# circuit.net
KiCad netlist of a schematic drawn in EAGLE
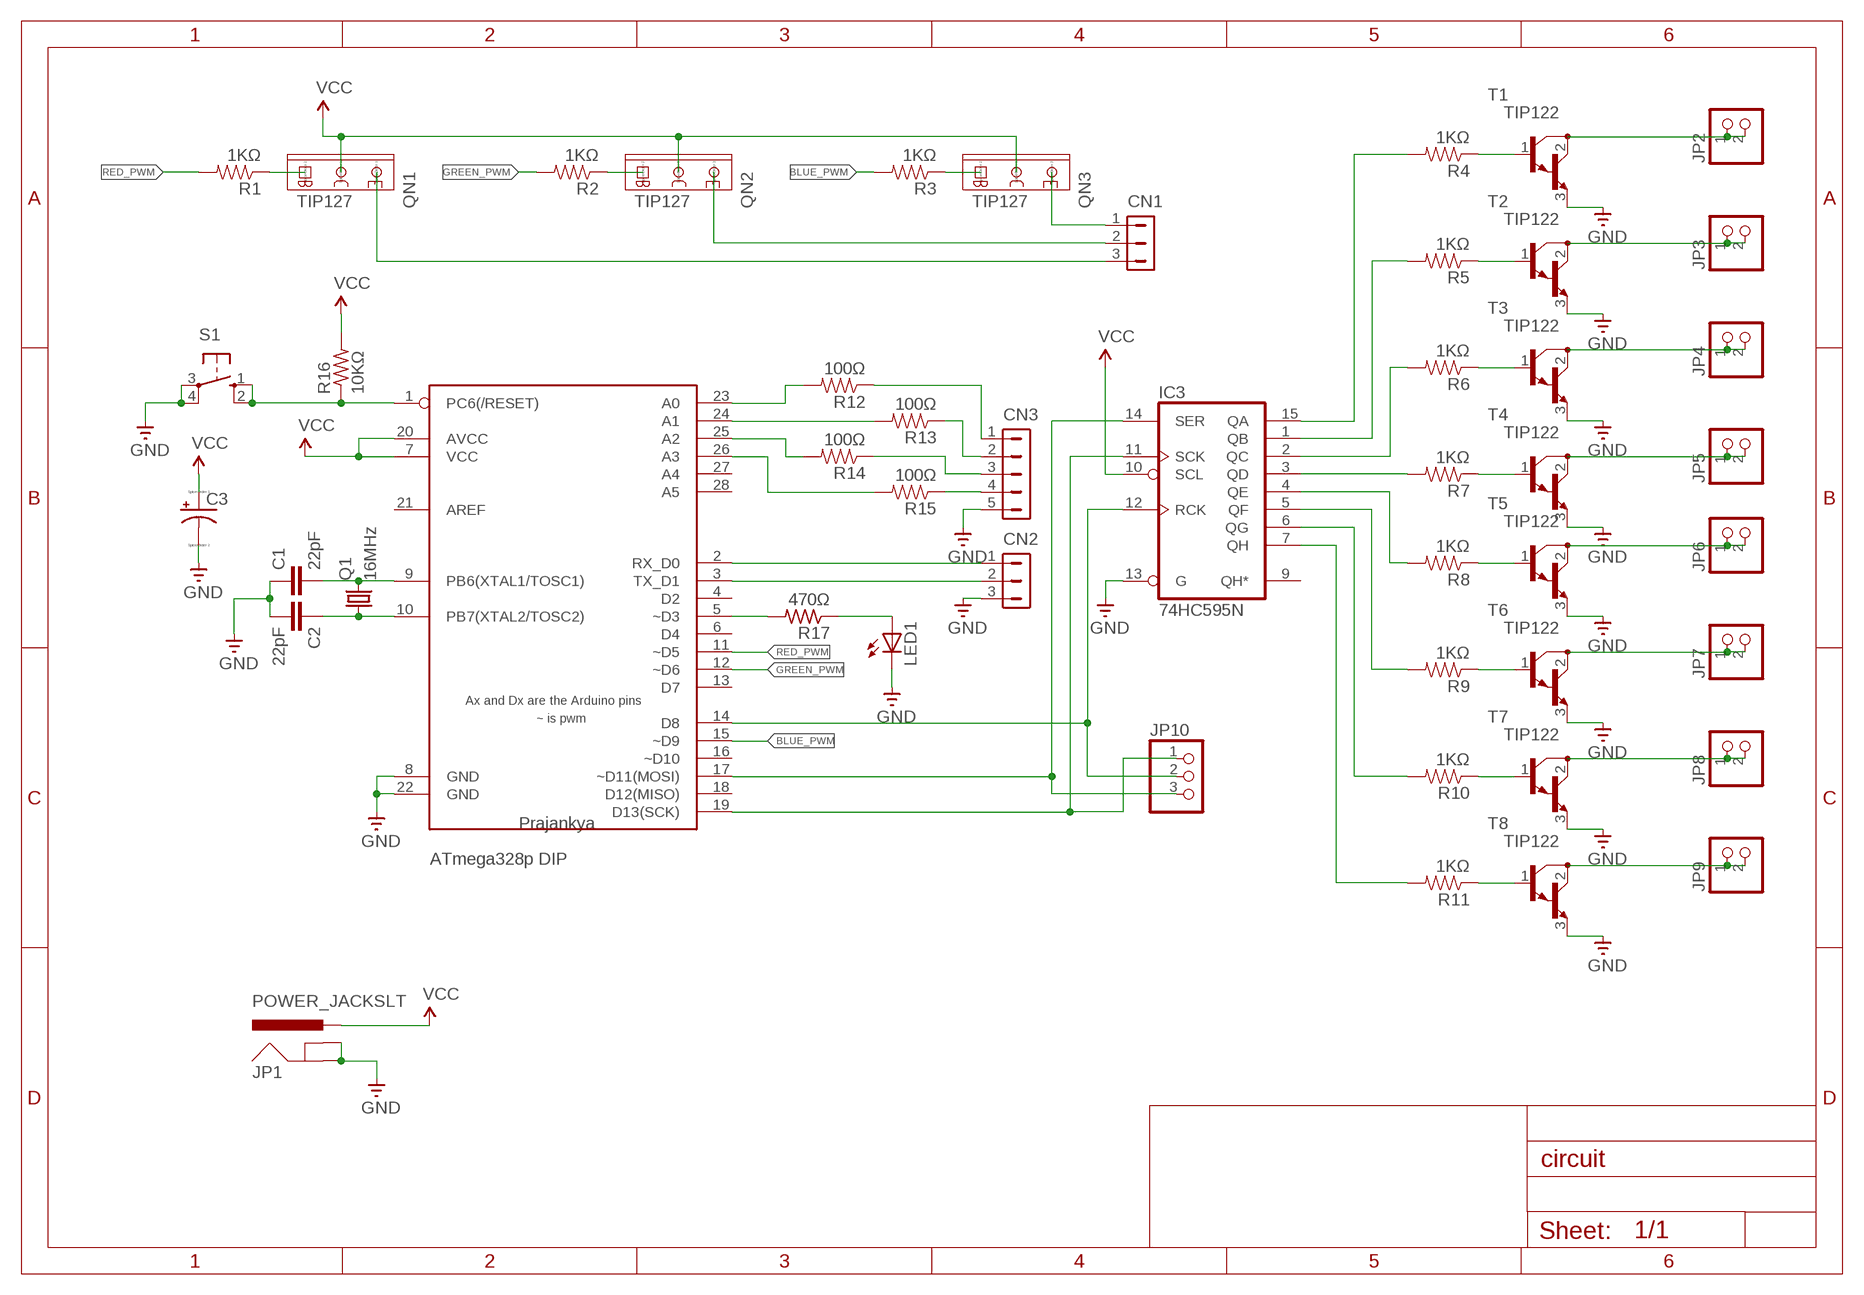
[diagram p0: schematic, sheet 1]

(export (version "E")
  (design (tool "Eeschema 10.0.6"))
  (components
    (comp (ref "C1")
      (value "22pF")
      (footprint "eagle-import:C025-025X050")
      (libsource (lib "eagle-import") (part "C-EU025-025X050"))
    )
    (comp (ref "C2")
      (value "22pF")
      (footprint "eagle-import:C025-025X050")
      (libsource (lib "eagle-import") (part "C-EU025-025X050"))
    )
    (comp (ref "C3")
      (value "CPOL-USTT2D6L")
      (footprint "eagle-import:TT2D6L")
      (libsource (lib "eagle-import") (part "CPOL-USTT2D6L"))
    )
    (comp (ref "CN1")
      (value "HDR-1X3-70543-?")
      (footprint "eagle-import:70543-03")
      (libsource (lib "eagle-import") (part "HDR-1X3-70543-?"))
    )
    (comp (ref "CN2")
      (value "HDR-1X3-70543-?")
      (footprint "eagle-import:70543-03")
      (libsource (lib "eagle-import") (part "HDR-1X3-70543-?"))
    )
    (comp (ref "CN3")
      (value "HDR-1X5-70543-?")
      (footprint "eagle-import:70543-05")
      (libsource (lib "eagle-import") (part "HDR-1X5-70543-?"))
    )
    (comp (ref "IC3")
      (value "74HC595N")
      (footprint "eagle-import:DIL16")
      (libsource (lib "eagle-import") (part "74595NHC"))
    )
    (comp (ref "JP1")
      (value "POWER_JACKSLT")
      (footprint "eagle-import:POWER_JACK_SLOT")
      (libsource (lib "eagle-import") (part "POWER_JACKSLT"))
    )
    (comp (ref "JP2")
      (value "PINHD-1X2")
      (footprint "eagle-import:1X02")
      (libsource (lib "eagle-import") (part "PINHD-1X2"))
    )
    (comp (ref "JP3")
      (value "PINHD-1X2")
      (footprint "eagle-import:1X02")
      (libsource (lib "eagle-import") (part "PINHD-1X2"))
    )
    (comp (ref "JP4")
      (value "PINHD-1X2")
      (footprint "eagle-import:1X02")
      (libsource (lib "eagle-import") (part "PINHD-1X2"))
    )
    (comp (ref "JP5")
      (value "PINHD-1X2")
      (footprint "eagle-import:1X02")
      (libsource (lib "eagle-import") (part "PINHD-1X2"))
    )
    (comp (ref "JP6")
      (value "PINHD-1X2")
      (footprint "eagle-import:1X02")
      (libsource (lib "eagle-import") (part "PINHD-1X2"))
    )
    (comp (ref "JP7")
      (value "PINHD-1X2")
      (footprint "eagle-import:1X02")
      (libsource (lib "eagle-import") (part "PINHD-1X2"))
    )
    (comp (ref "JP8")
      (value "PINHD-1X2")
      (footprint "eagle-import:1X02")
      (libsource (lib "eagle-import") (part "PINHD-1X2"))
    )
    (comp (ref "JP9")
      (value "PINHD-1X2")
      (footprint "eagle-import:1X02")
      (libsource (lib "eagle-import") (part "PINHD-1X2"))
    )
    (comp (ref "JP10")
      (value "PINHD-1X3")
      (footprint "eagle-import:1X03")
      (libsource (lib "eagle-import") (part "PINHD-1X3"))
    )
    (comp (ref "LED1")
      (value "LED5MM")
      (footprint "eagle-import:LED5MM")
      (libsource (lib "eagle-import") (part "LED5MM"))
    )
    (comp (ref "Q1")
      (value "16MHz")
      (footprint "eagle-import:HC49U-V")
      (libsource (lib "eagle-import") (part "CRYSTALHC49U-V"))
    )
    (comp (ref "QN1")
      (value "TIP127")
      (footprint "eagle-import:TO220AV")
      (libsource (lib "eagle-import") (part "TIP127"))
    )
    (comp (ref "QN2")
      (value "TIP127")
      (footprint "eagle-import:TO220AV")
      (libsource (lib "eagle-import") (part "TIP127"))
    )
    (comp (ref "QN3")
      (value "TIP127")
      (footprint "eagle-import:TO220AV")
      (libsource (lib "eagle-import") (part "TIP127"))
    )
    (comp (ref "R1")
      (value "1KΩ")
      (footprint "eagle-import:AXIAL-0.4")
      (libsource (lib "eagle-import") (part "RESISTORPTH-1/4W"))
    )
    (comp (ref "R2")
      (value "1KΩ")
      (footprint "eagle-import:AXIAL-0.4")
      (libsource (lib "eagle-import") (part "RESISTORPTH-1/4W"))
    )
    (comp (ref "R3")
      (value "1KΩ")
      (footprint "eagle-import:AXIAL-0.4")
      (libsource (lib "eagle-import") (part "RESISTORPTH-1/4W"))
    )
    (comp (ref "R4")
      (value "1KΩ")
      (footprint "eagle-import:AXIAL-0.4")
      (libsource (lib "eagle-import") (part "RESISTORPTH-1/4W"))
    )
    (comp (ref "R5")
      (value "1KΩ")
      (footprint "eagle-import:AXIAL-0.4")
      (libsource (lib "eagle-import") (part "RESISTORPTH-1/4W"))
    )
    (comp (ref "R6")
      (value "1KΩ")
      (footprint "eagle-import:AXIAL-0.4")
      (libsource (lib "eagle-import") (part "RESISTORPTH-1/4W"))
    )
    (comp (ref "R7")
      (value "1KΩ")
      (footprint "eagle-import:AXIAL-0.4")
      (libsource (lib "eagle-import") (part "RESISTORPTH-1/4W"))
    )
    (comp (ref "R8")
      (value "1KΩ")
      (footprint "eagle-import:AXIAL-0.4")
      (libsource (lib "eagle-import") (part "RESISTORPTH-1/4W"))
    )
    (comp (ref "R9")
      (value "1KΩ")
      (footprint "eagle-import:AXIAL-0.4")
      (libsource (lib "eagle-import") (part "RESISTORPTH-1/4W"))
    )
    (comp (ref "R10")
      (value "1KΩ")
      (footprint "eagle-import:AXIAL-0.4")
      (libsource (lib "eagle-import") (part "RESISTORPTH-1/4W"))
    )
    (comp (ref "R11")
      (value "1KΩ")
      (footprint "eagle-import:AXIAL-0.4")
      (libsource (lib "eagle-import") (part "RESISTORPTH-1/4W"))
    )
    (comp (ref "R12")
      (value "100Ω")
      (footprint "eagle-import:AXIAL-0.4")
      (libsource (lib "eagle-import") (part "RESISTORPTH-1/4W"))
    )
    (comp (ref "R13")
      (value "100Ω")
      (footprint "eagle-import:AXIAL-0.4")
      (libsource (lib "eagle-import") (part "RESISTORPTH-1/4W"))
    )
    (comp (ref "R14")
      (value "100Ω")
      (footprint "eagle-import:AXIAL-0.4")
      (libsource (lib "eagle-import") (part "RESISTORPTH-1/4W"))
    )
    (comp (ref "R15")
      (value "100Ω")
      (footprint "eagle-import:AXIAL-0.4")
      (libsource (lib "eagle-import") (part "RESISTORPTH-1/4W"))
    )
    (comp (ref "R16")
      (value "10KΩ")
      (footprint "eagle-import:0207_10")
      (libsource (lib "eagle-import") (part "R-US_0207/10"))
    )
    (comp (ref "R17")
      (value "470Ω")
      (footprint "eagle-import:0207_12")
      (libsource (lib "eagle-import") (part "R-US_0207/12"))
    )
    (comp (ref "S1")
      (value "10-XX")
      (footprint "eagle-import:B3F-10XX")
      (fields (field (name "MPN") "B3F-1000"))
      (libsource (lib "eagle-import") (part "10-XX"))
    )
    (comp (ref "T1")
      (value "TIP122")
      (footprint "eagle-import:TO220")
      (libsource (lib "eagle-import") (part "TIP122"))
    )
    (comp (ref "T2")
      (value "TIP122")
      (footprint "eagle-import:TO220")
      (libsource (lib "eagle-import") (part "TIP122"))
    )
    (comp (ref "T3")
      (value "TIP122")
      (footprint "eagle-import:TO220")
      (libsource (lib "eagle-import") (part "TIP122"))
    )
    (comp (ref "T4")
      (value "TIP122")
      (footprint "eagle-import:TO220")
      (libsource (lib "eagle-import") (part "TIP122"))
    )
    (comp (ref "T5")
      (value "TIP122")
      (footprint "eagle-import:TO220")
      (libsource (lib "eagle-import") (part "TIP122"))
    )
    (comp (ref "T6")
      (value "TIP122")
      (footprint "eagle-import:TO220")
      (libsource (lib "eagle-import") (part "TIP122"))
    )
    (comp (ref "T7")
      (value "TIP122")
      (footprint "eagle-import:TO220")
      (libsource (lib "eagle-import") (part "TIP122"))
    )
    (comp (ref "T8")
      (value "TIP122")
      (footprint "eagle-import:TO220")
      (libsource (lib "eagle-import") (part "TIP122"))
    )
    (comp (ref "U$1")
      (value "ATMEGA328P_DIP")
      (footprint "eagle-import:ATMEGA328_CUSTOMPAD")
      (libsource (lib "eagle-import") (part "ATMEGA328P_DIP"))
    )
  )
  (nets
    (net (code "1") (name "BLUE_PWM") (class "Default")
      (node (ref "R3") (pin "P$2") (pinfunction "2_P$2") (pintype "passive"))
      (node (ref "U$1") (pin "15") (pinfunction "~{D9}_15") (pintype "bidirectional"))
    )
    (net (code "2") (name "GND") (class "Default")
      (node (ref "C1") (pin "1") (pinfunction "1_1") (pintype "passive"))
      (node (ref "C2") (pin "2") (pinfunction "2_2") (pintype "passive"))
      (node (ref "C3") (pin "-") (pinfunction "-_-") (pintype "passive"))
      (node (ref "CN2") (pin "3") (pinfunction "3_3") (pintype "passive"))
      (node (ref "CN3") (pin "5") (pinfunction "5_5") (pintype "passive"))
      (node (ref "IC3") (pin "13") (pinfunction "G_13") (pintype "input"))
      (node (ref "JP1") (pin "GND@1") (pinfunction "GNDBREAK_GND@1") (pintype "bidirectional"))
      (node (ref "JP1") (pin "GND@2") (pinfunction "GND_GND@2") (pintype "bidirectional"))
      (node (ref "LED1") (pin "K") (pinfunction "C_K") (pintype "passive"))
      (node (ref "S1") (pin "3") (pinfunction "P_3") (pintype "passive"))
      (node (ref "S1") (pin "4") (pinfunction "P1_4") (pintype "passive"))
      (node (ref "T1") (pin "3") (pinfunction "E_3") (pintype "passive"))
      (node (ref "T2") (pin "3") (pinfunction "E_3") (pintype "passive"))
      (node (ref "T3") (pin "3") (pinfunction "E_3") (pintype "passive"))
      (node (ref "T4") (pin "3") (pinfunction "E_3") (pintype "passive"))
      (node (ref "T5") (pin "3") (pinfunction "E_3") (pintype "passive"))
      (node (ref "T6") (pin "3") (pinfunction "E_3") (pintype "passive"))
      (node (ref "T7") (pin "3") (pinfunction "E_3") (pintype "passive"))
      (node (ref "T8") (pin "3") (pinfunction "E_3") (pintype "passive"))
      (node (ref "U$1") (pin "22") (pinfunction "GND_22") (pintype "power_in"))
      (node (ref "U$1") (pin "8") (pinfunction "GND_8") (pintype "power_in"))
    )
    (net (code "3") (name "GREEN_PWM") (class "Default")
      (node (ref "R2") (pin "P$2") (pinfunction "2_P$2") (pintype "passive"))
      (node (ref "U$1") (pin "12") (pinfunction "~{D6}_12") (pintype "bidirectional"))
    )
    (net (code "4") (name "Net-(CN1-Pad1)") (class "Default")
      (node (ref "CN1") (pin "1") (pinfunction "1_1") (pintype "passive"))
      (node (ref "QN3") (pin "E") (pinfunction "E_E") (pintype "passive"))
    )
    (net (code "5") (name "Net-(CN1-Pad2)") (class "Default")
      (node (ref "CN1") (pin "2") (pinfunction "2_2") (pintype "passive"))
      (node (ref "QN2") (pin "E") (pinfunction "E_E") (pintype "passive"))
    )
    (net (code "6") (name "Net-(CN1-Pad3)") (class "Default")
      (node (ref "CN1") (pin "3") (pinfunction "3_3") (pintype "passive"))
      (node (ref "QN1") (pin "E") (pinfunction "E_E") (pintype "passive"))
    )
    (net (code "7") (name "Net-(IC3A-QA)") (class "Default")
      (node (ref "IC3") (pin "15") (pinfunction "QA_15") (pintype "tri_state"))
      (node (ref "R4") (pin "P$2") (pinfunction "2_P$2") (pintype "passive"))
    )
    (net (code "8") (name "Net-(IC3A-QB)") (class "Default")
      (node (ref "IC3") (pin "1") (pinfunction "QB_1") (pintype "tri_state"))
      (node (ref "R5") (pin "P$2") (pinfunction "2_P$2") (pintype "passive"))
    )
    (net (code "9") (name "Net-(IC3A-QC)") (class "Default")
      (node (ref "IC3") (pin "2") (pinfunction "QC_2") (pintype "tri_state"))
      (node (ref "R6") (pin "P$2") (pinfunction "2_P$2") (pintype "passive"))
    )
    (net (code "10") (name "Net-(IC3A-QD)") (class "Default")
      (node (ref "IC3") (pin "3") (pinfunction "QD_3") (pintype "tri_state"))
      (node (ref "R7") (pin "P$2") (pinfunction "2_P$2") (pintype "passive"))
    )
    (net (code "11") (name "Net-(IC3A-QE)") (class "Default")
      (node (ref "IC3") (pin "4") (pinfunction "QE_4") (pintype "tri_state"))
      (node (ref "R8") (pin "P$2") (pinfunction "2_P$2") (pintype "passive"))
    )
    (net (code "12") (name "Net-(IC3A-QF)") (class "Default")
      (node (ref "IC3") (pin "5") (pinfunction "QF_5") (pintype "tri_state"))
      (node (ref "R9") (pin "P$2") (pinfunction "2_P$2") (pintype "passive"))
    )
    (net (code "13") (name "Net-(IC3A-QG)") (class "Default")
      (node (ref "IC3") (pin "6") (pinfunction "QG_6") (pintype "tri_state"))
      (node (ref "R10") (pin "P$2") (pinfunction "2_P$2") (pintype "passive"))
    )
    (net (code "14") (name "Net-(IC3A-QH)") (class "Default")
      (node (ref "IC3") (pin "7") (pinfunction "QH_7") (pintype "tri_state"))
      (node (ref "R11") (pin "P$2") (pinfunction "2_P$2") (pintype "passive"))
    )
    (net (code "15") (name "Net-(IC3A-RCK)") (class "Default")
      (node (ref "IC3") (pin "12") (pinfunction "RCK_12") (pintype "input"))
      (node (ref "JP10") (pin "2") (pinfunction "2_2") (pintype "passive"))
      (node (ref "U$1") (pin "14") (pinfunction "D8_14") (pintype "bidirectional"))
    )
    (net (code "16") (name "Net-(IC3A-SCK)") (class "Default")
      (node (ref "IC3") (pin "11") (pinfunction "SCK_11") (pintype "input"))
      (node (ref "JP10") (pin "1") (pinfunction "1_1") (pintype "passive"))
      (node (ref "U$1") (pin "19") (pinfunction "D13(SCK)_19") (pintype "bidirectional"))
    )
    (net (code "17") (name "Net-(IC3A-SER)") (class "Default")
      (node (ref "IC3") (pin "14") (pinfunction "SER_14") (pintype "input"))
      (node (ref "JP10") (pin "3") (pinfunction "3_3") (pintype "passive"))
      (node (ref "U$1") (pin "17") (pinfunction "~{D11(MOSI})_17") (pintype "bidirectional"))
    )
    (net (code "18") (name "Net-(LED1-PadA)") (class "Default")
      (node (ref "LED1") (pin "A") (pinfunction "A_A") (pintype "passive"))
      (node (ref "R17") (pin "1") (pinfunction "1_1") (pintype "passive"))
    )
    (net (code "19") (name "Net-(R1-1)") (class "Default")
      (node (ref "QN1") (pin "B") (pinfunction "B_B") (pintype "passive"))
      (node (ref "R1") (pin "P$1") (pinfunction "1_P$1") (pintype "passive"))
    )
    (net (code "20") (name "Net-(R2-1)") (class "Default")
      (node (ref "QN2") (pin "B") (pinfunction "B_B") (pintype "passive"))
      (node (ref "R2") (pin "P$1") (pinfunction "1_P$1") (pintype "passive"))
    )
    (net (code "21") (name "Net-(R3-1)") (class "Default")
      (node (ref "QN3") (pin "B") (pinfunction "B_B") (pintype "passive"))
      (node (ref "R3") (pin "P$1") (pinfunction "1_P$1") (pintype "passive"))
    )
    (net (code "22") (name "Net-(R4-1)") (class "Default")
      (node (ref "R4") (pin "P$1") (pinfunction "1_P$1") (pintype "passive"))
      (node (ref "T1") (pin "1") (pinfunction "B_1") (pintype "passive"))
    )
    (net (code "23") (name "Net-(R5-1)") (class "Default")
      (node (ref "R5") (pin "P$1") (pinfunction "1_P$1") (pintype "passive"))
      (node (ref "T2") (pin "1") (pinfunction "B_1") (pintype "passive"))
    )
    (net (code "24") (name "Net-(R6-1)") (class "Default")
      (node (ref "R6") (pin "P$1") (pinfunction "1_P$1") (pintype "passive"))
      (node (ref "T3") (pin "1") (pinfunction "B_1") (pintype "passive"))
    )
    (net (code "25") (name "Net-(R7-1)") (class "Default")
      (node (ref "R7") (pin "P$1") (pinfunction "1_P$1") (pintype "passive"))
      (node (ref "T4") (pin "1") (pinfunction "B_1") (pintype "passive"))
    )
    (net (code "26") (name "Net-(R8-1)") (class "Default")
      (node (ref "R8") (pin "P$1") (pinfunction "1_P$1") (pintype "passive"))
      (node (ref "T5") (pin "1") (pinfunction "B_1") (pintype "passive"))
    )
    (net (code "27") (name "Net-(R9-1)") (class "Default")
      (node (ref "R9") (pin "P$1") (pinfunction "1_P$1") (pintype "passive"))
      (node (ref "T6") (pin "1") (pinfunction "B_1") (pintype "passive"))
    )
    (net (code "28") (name "Net-(R10-1)") (class "Default")
      (node (ref "R10") (pin "P$1") (pinfunction "1_P$1") (pintype "passive"))
      (node (ref "T7") (pin "1") (pinfunction "B_1") (pintype "passive"))
    )
    (net (code "29") (name "Net-(R11-1)") (class "Default")
      (node (ref "R11") (pin "P$1") (pinfunction "1_P$1") (pintype "passive"))
      (node (ref "T8") (pin "1") (pinfunction "B_1") (pintype "passive"))
    )
    (net (code "30") (name "Net-(R12-1)") (class "Default")
      (node (ref "CN3") (pin "1") (pinfunction "1_1") (pintype "passive"))
      (node (ref "R12") (pin "P$1") (pinfunction "1_P$1") (pintype "passive"))
    )
    (net (code "31") (name "Net-(R12-2)") (class "Default")
      (node (ref "R12") (pin "P$2") (pinfunction "2_P$2") (pintype "passive"))
      (node (ref "U$1") (pin "23") (pinfunction "A0_23") (pintype "bidirectional"))
    )
    (net (code "32") (name "Net-(R13-1)") (class "Default")
      (node (ref "CN3") (pin "2") (pinfunction "2_2") (pintype "passive"))
      (node (ref "R13") (pin "P$1") (pinfunction "1_P$1") (pintype "passive"))
    )
    (net (code "33") (name "Net-(R13-2)") (class "Default")
      (node (ref "R13") (pin "P$2") (pinfunction "2_P$2") (pintype "passive"))
      (node (ref "U$1") (pin "24") (pinfunction "A1_24") (pintype "bidirectional"))
    )
    (net (code "34") (name "Net-(R14-1)") (class "Default")
      (node (ref "CN3") (pin "3") (pinfunction "3_3") (pintype "passive"))
      (node (ref "R14") (pin "P$1") (pinfunction "1_P$1") (pintype "passive"))
    )
    (net (code "35") (name "Net-(R14-2)") (class "Default")
      (node (ref "R14") (pin "P$2") (pinfunction "2_P$2") (pintype "passive"))
      (node (ref "U$1") (pin "25") (pinfunction "A2_25") (pintype "bidirectional"))
    )
    (net (code "36") (name "Net-(R15-1)") (class "Default")
      (node (ref "CN3") (pin "4") (pinfunction "4_4") (pintype "passive"))
      (node (ref "R15") (pin "P$1") (pinfunction "1_P$1") (pintype "passive"))
    )
    (net (code "37") (name "Net-(R15-2)") (class "Default")
      (node (ref "R15") (pin "P$2") (pinfunction "2_P$2") (pintype "passive"))
      (node (ref "U$1") (pin "26") (pinfunction "A3_26") (pintype "bidirectional"))
    )
    (net (code "38") (name "Net-(S1-S)") (class "Default")
      (node (ref "R16") (pin "1") (pinfunction "1_1") (pintype "passive"))
      (node (ref "S1") (pin "1") (pinfunction "S_1") (pintype "passive"))
      (node (ref "S1") (pin "2") (pinfunction "S1_2") (pintype "passive"))
      (node (ref "U$1") (pin "1") (pinfunction "PC6(/RESET)_1") (pintype "bidirectional"))
    )
    (net (code "39") (name "Net-(T1-C)") (class "Default")
      (node (ref "JP2") (pin "1") (pinfunction "1_1") (pintype "passive"))
      (node (ref "JP2") (pin "2") (pinfunction "2_2") (pintype "passive"))
      (node (ref "T1") (pin "2") (pinfunction "C_2") (pintype "passive"))
    )
    (net (code "40") (name "Net-(T2-C)") (class "Default")
      (node (ref "JP3") (pin "1") (pinfunction "1_1") (pintype "passive"))
      (node (ref "JP3") (pin "2") (pinfunction "2_2") (pintype "passive"))
      (node (ref "T2") (pin "2") (pinfunction "C_2") (pintype "passive"))
    )
    (net (code "41") (name "Net-(T3-C)") (class "Default")
      (node (ref "JP4") (pin "1") (pinfunction "1_1") (pintype "passive"))
      (node (ref "JP4") (pin "2") (pinfunction "2_2") (pintype "passive"))
      (node (ref "T3") (pin "2") (pinfunction "C_2") (pintype "passive"))
    )
    (net (code "42") (name "Net-(T4-C)") (class "Default")
      (node (ref "JP5") (pin "1") (pinfunction "1_1") (pintype "passive"))
      (node (ref "JP5") (pin "2") (pinfunction "2_2") (pintype "passive"))
      (node (ref "T4") (pin "2") (pinfunction "C_2") (pintype "passive"))
    )
    (net (code "43") (name "Net-(T5-C)") (class "Default")
      (node (ref "JP6") (pin "1") (pinfunction "1_1") (pintype "passive"))
      (node (ref "JP6") (pin "2") (pinfunction "2_2") (pintype "passive"))
      (node (ref "T5") (pin "2") (pinfunction "C_2") (pintype "passive"))
    )
    (net (code "44") (name "Net-(T6-C)") (class "Default")
      (node (ref "JP7") (pin "1") (pinfunction "1_1") (pintype "passive"))
      (node (ref "JP7") (pin "2") (pinfunction "2_2") (pintype "passive"))
      (node (ref "T6") (pin "2") (pinfunction "C_2") (pintype "passive"))
    )
    (net (code "45") (name "Net-(T7-C)") (class "Default")
      (node (ref "JP8") (pin "1") (pinfunction "1_1") (pintype "passive"))
      (node (ref "JP8") (pin "2") (pinfunction "2_2") (pintype "passive"))
      (node (ref "T7") (pin "2") (pinfunction "C_2") (pintype "passive"))
    )
    (net (code "46") (name "Net-(T8-C)") (class "Default")
      (node (ref "JP9") (pin "1") (pinfunction "1_1") (pintype "passive"))
      (node (ref "JP9") (pin "2") (pinfunction "2_2") (pintype "passive"))
      (node (ref "T8") (pin "2") (pinfunction "C_2") (pintype "passive"))
    )
    (net (code "47") (name "Net-(U$1-PB6(XTAL1{slash}TOSC1))") (class "Default")
      (node (ref "C1") (pin "2") (pinfunction "2_2") (pintype "passive"))
      (node (ref "Q1") (pin "2") (pinfunction "2_2") (pintype "passive"))
      (node (ref "U$1") (pin "9") (pinfunction "PB6(XTAL1/TOSC1)_9") (pintype "bidirectional"))
    )
    (net (code "48") (name "Net-(U$1-PB7(XTAL2{slash}TOSC2))") (class "Default")
      (node (ref "C2") (pin "1") (pinfunction "1_1") (pintype "passive"))
      (node (ref "Q1") (pin "1") (pinfunction "1_1") (pintype "passive"))
      (node (ref "U$1") (pin "10") (pinfunction "PB7(XTAL2/TOSC2)_10") (pintype "bidirectional"))
    )
    (net (code "49") (name "Net-(U$1-RX_D0)") (class "Default")
      (node (ref "CN2") (pin "1") (pinfunction "1_1") (pintype "passive"))
      (node (ref "U$1") (pin "2") (pinfunction "RX_D0_2") (pintype "input"))
    )
    (net (code "50") (name "Net-(U$1-TX_D1)") (class "Default")
      (node (ref "CN2") (pin "2") (pinfunction "2_2") (pintype "passive"))
      (node (ref "U$1") (pin "3") (pinfunction "TX_D1_3") (pintype "output"))
    )
    (net (code "51") (name "Net-(U$1-~{D3})") (class "Default")
      (node (ref "R17") (pin "2") (pinfunction "2_2") (pintype "passive"))
      (node (ref "U$1") (pin "5") (pinfunction "~{D3}_5") (pintype "bidirectional"))
    )
    (net (code "52") (name "RED_PWM") (class "Default")
      (node (ref "R1") (pin "P$2") (pinfunction "2_P$2") (pintype "passive"))
      (node (ref "U$1") (pin "11") (pinfunction "~{D5}_11") (pintype "bidirectional"))
    )
    (net (code "53") (name "VCC") (class "Default")
      (node (ref "C3") (pin "+") (pinfunction "+_+") (pintype "passive"))
      (node (ref "IC3") (pin "10") (pinfunction "SCL_10") (pintype "input"))
      (node (ref "JP1") (pin "PWR") (pinfunction "PWR_PWR") (pintype "bidirectional"))
      (node (ref "QN1") (pin "C") (pinfunction "C_C") (pintype "passive"))
      (node (ref "QN2") (pin "C") (pinfunction "C_C") (pintype "passive"))
      (node (ref "QN3") (pin "C") (pinfunction "C_C") (pintype "passive"))
      (node (ref "R16") (pin "2") (pinfunction "2_2") (pintype "passive"))
      (node (ref "U$1") (pin "20") (pinfunction "AVCC_20") (pintype "power_in"))
      (node (ref "U$1") (pin "7") (pinfunction "VCC_7") (pintype "power_in"))
    )
    (net (code "54") (name "unconnected-(IC3A-QH*-Pad9)") (class "Default")
      (node (ref "IC3") (pin "9") (pinfunction "QH*_9") (pintype "tri_state"))
    )
    (net (code "55") (name "unconnected-(U$1-A4-Pad27)") (class "Default")
      (node (ref "U$1") (pin "27") (pinfunction "A4_27") (pintype "bidirectional"))
    )
    (net (code "56") (name "unconnected-(U$1-A5-Pad28)") (class "Default")
      (node (ref "U$1") (pin "28") (pinfunction "A5_28") (pintype "bidirectional"))
    )
    (net (code "57") (name "unconnected-(U$1-AREF-Pad21)") (class "Default")
      (node (ref "U$1") (pin "21") (pinfunction "AREF_21") (pintype "bidirectional"))
    )
    (net (code "58") (name "unconnected-(U$1-D2-Pad4)") (class "Default")
      (node (ref "U$1") (pin "4") (pinfunction "D2_4") (pintype "bidirectional"))
    )
    (net (code "59") (name "unconnected-(U$1-D4-Pad6)") (class "Default")
      (node (ref "U$1") (pin "6") (pinfunction "D4_6") (pintype "bidirectional"))
    )
    (net (code "60") (name "unconnected-(U$1-D7-Pad13)") (class "Default")
      (node (ref "U$1") (pin "13") (pinfunction "D7_13") (pintype "bidirectional"))
    )
    (net (code "61") (name "unconnected-(U$1-D12(MISO)-Pad18)") (class "Default")
      (node (ref "U$1") (pin "18") (pinfunction "D12(MISO)_18") (pintype "bidirectional"))
    )
    (net (code "62") (name "unconnected-(U$1-~{D10}-Pad16)") (class "Default")
      (node (ref "U$1") (pin "16") (pinfunction "~{D10}_16") (pintype "bidirectional"))
    )
  )
)
